# rc2014_3kb_ram.net
KiCad netlist of a schematic drawn in EAGLE
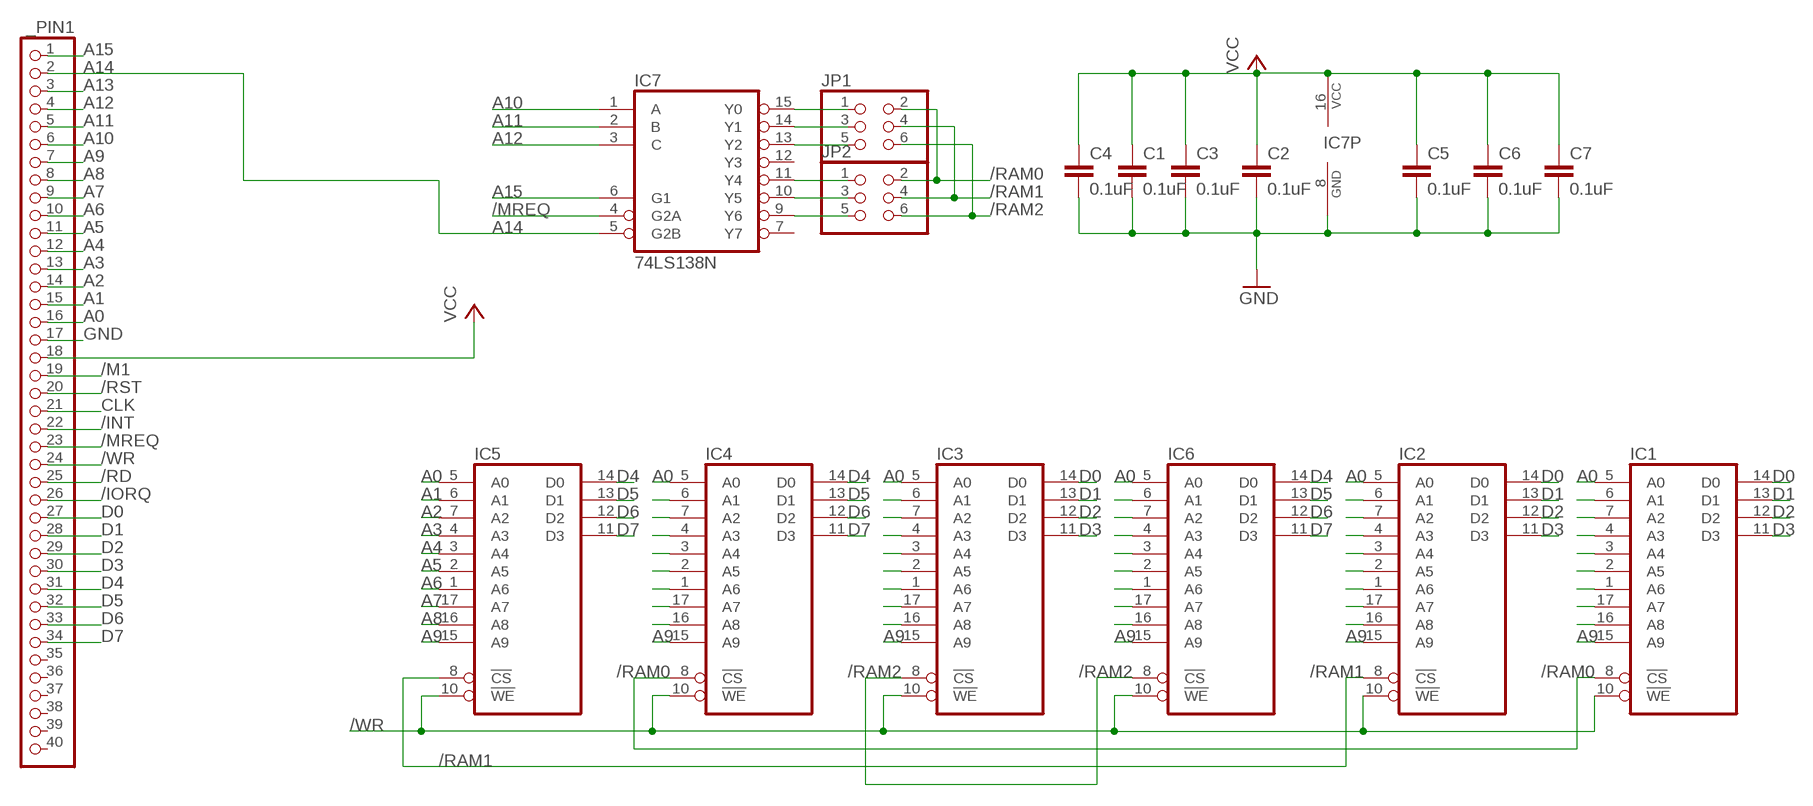
[diagram p0: schematic, sheet 1]

(export (version "E")
  (design (tool "Eeschema 10.0.6"))
  (components
    (comp (ref "C1")
      (value "0.1uF")
      (footprint "eagle-import:C050-024X044")
      (libsource (lib "eagle-import") (part "C-EU050-024X044"))
    )
    (comp (ref "C2")
      (value "0.1uF")
      (footprint "eagle-import:C050-024X044")
      (libsource (lib "eagle-import") (part "C-EU050-024X044"))
    )
    (comp (ref "C3")
      (value "0.1uF")
      (footprint "eagle-import:C050-024X044")
      (libsource (lib "eagle-import") (part "C-EU050-024X044"))
    )
    (comp (ref "C4")
      (value "0.1uF")
      (footprint "eagle-import:C050-024X044")
      (libsource (lib "eagle-import") (part "C-EU050-024X044"))
    )
    (comp (ref "C5")
      (value "0.1uF")
      (footprint "eagle-import:C050-024X044")
      (libsource (lib "eagle-import") (part "C-EU050-024X044"))
    )
    (comp (ref "C6")
      (value "0.1uF")
      (footprint "eagle-import:C050-024X044")
      (libsource (lib "eagle-import") (part "C-EU050-024X044"))
    )
    (comp (ref "C7")
      (value "0.1uF")
      (footprint "eagle-import:C050-024X044")
      (libsource (lib "eagle-import") (part "C-EU050-024X044"))
    )
    (comp (ref "IC1")
      (value "2114")
      (footprint "eagle-import:DIL18")
      (libsource (lib "eagle-import") (part "2114"))
    )
    (comp (ref "IC2")
      (value "2114")
      (footprint "eagle-import:DIL18")
      (libsource (lib "eagle-import") (part "2114"))
    )
    (comp (ref "IC3")
      (value "2114")
      (footprint "eagle-import:DIL18")
      (libsource (lib "eagle-import") (part "2114"))
    )
    (comp (ref "IC4")
      (value "2114")
      (footprint "eagle-import:DIL18")
      (libsource (lib "eagle-import") (part "2114"))
    )
    (comp (ref "IC5")
      (value "2114")
      (footprint "eagle-import:DIL18")
      (libsource (lib "eagle-import") (part "2114"))
    )
    (comp (ref "IC6")
      (value "2114")
      (footprint "eagle-import:DIL18")
      (libsource (lib "eagle-import") (part "2114"))
    )
    (comp (ref "IC7")
      (value "74LS138N")
      (footprint "eagle-import:DIL16")
      (libsource (lib "eagle-import") (part "74138NLS"))
    )
    (comp (ref "JP1")
      (value "PINHD-2X3")
      (footprint "eagle-import:2X03")
      (libsource (lib "eagle-import") (part "PINHD-2X3"))
    )
    (comp (ref "JP2")
      (value "PINHD-2X3")
      (footprint "eagle-import:2X03")
      (libsource (lib "eagle-import") (part "PINHD-2X3"))
    )
    (comp (ref "_PIN1")
      (value "PINHD-1X40")
      (footprint "eagle-import:1X40")
      (libsource (lib "eagle-import") (part "PINHD-1X40"))
    )
  )
  (nets
    (net (code "1") (name "/A0") (class "Default")
      (node (ref "IC1") (pin "5") (pinfunction "A0_5") (pintype "input"))
      (node (ref "IC2") (pin "5") (pinfunction "A0_5") (pintype "input"))
      (node (ref "IC3") (pin "5") (pinfunction "A0_5") (pintype "input"))
      (node (ref "IC4") (pin "5") (pinfunction "A0_5") (pintype "input"))
      (node (ref "IC5") (pin "5") (pinfunction "A0_5") (pintype "input"))
      (node (ref "IC6") (pin "5") (pinfunction "A0_5") (pintype "input"))
      (node (ref "_PIN1") (pin "16") (pinfunction "16_16") (pintype "passive"))
    )
    (net (code "2") (name "/A1") (class "Default")
      (node (ref "IC1") (pin "6") (pinfunction "A1_6") (pintype "input"))
      (node (ref "IC2") (pin "6") (pinfunction "A1_6") (pintype "input"))
      (node (ref "IC3") (pin "6") (pinfunction "A1_6") (pintype "input"))
      (node (ref "IC4") (pin "6") (pinfunction "A1_6") (pintype "input"))
      (node (ref "IC5") (pin "6") (pinfunction "A1_6") (pintype "input"))
      (node (ref "IC6") (pin "6") (pinfunction "A1_6") (pintype "input"))
      (node (ref "_PIN1") (pin "15") (pinfunction "15_15") (pintype "passive"))
    )
    (net (code "3") (name "/A2") (class "Default")
      (node (ref "IC1") (pin "7") (pinfunction "A2_7") (pintype "input"))
      (node (ref "IC2") (pin "7") (pinfunction "A2_7") (pintype "input"))
      (node (ref "IC3") (pin "7") (pinfunction "A2_7") (pintype "input"))
      (node (ref "IC4") (pin "7") (pinfunction "A2_7") (pintype "input"))
      (node (ref "IC5") (pin "7") (pinfunction "A2_7") (pintype "input"))
      (node (ref "IC6") (pin "7") (pinfunction "A2_7") (pintype "input"))
      (node (ref "_PIN1") (pin "14") (pinfunction "14_14") (pintype "passive"))
    )
    (net (code "4") (name "/A3") (class "Default")
      (node (ref "IC1") (pin "4") (pinfunction "A3_4") (pintype "input"))
      (node (ref "IC2") (pin "4") (pinfunction "A3_4") (pintype "input"))
      (node (ref "IC3") (pin "4") (pinfunction "A3_4") (pintype "input"))
      (node (ref "IC4") (pin "4") (pinfunction "A3_4") (pintype "input"))
      (node (ref "IC5") (pin "4") (pinfunction "A3_4") (pintype "input"))
      (node (ref "IC6") (pin "4") (pinfunction "A3_4") (pintype "input"))
      (node (ref "_PIN1") (pin "13") (pinfunction "13_13") (pintype "passive"))
    )
    (net (code "5") (name "/A4") (class "Default")
      (node (ref "IC1") (pin "3") (pinfunction "A4_3") (pintype "input"))
      (node (ref "IC2") (pin "3") (pinfunction "A4_3") (pintype "input"))
      (node (ref "IC3") (pin "3") (pinfunction "A4_3") (pintype "input"))
      (node (ref "IC4") (pin "3") (pinfunction "A4_3") (pintype "input"))
      (node (ref "IC5") (pin "3") (pinfunction "A4_3") (pintype "input"))
      (node (ref "IC6") (pin "3") (pinfunction "A4_3") (pintype "input"))
      (node (ref "_PIN1") (pin "12") (pinfunction "12_12") (pintype "passive"))
    )
    (net (code "6") (name "/A5") (class "Default")
      (node (ref "IC1") (pin "2") (pinfunction "A5_2") (pintype "input"))
      (node (ref "IC2") (pin "2") (pinfunction "A5_2") (pintype "input"))
      (node (ref "IC3") (pin "2") (pinfunction "A5_2") (pintype "input"))
      (node (ref "IC4") (pin "2") (pinfunction "A5_2") (pintype "input"))
      (node (ref "IC5") (pin "2") (pinfunction "A5_2") (pintype "input"))
      (node (ref "IC6") (pin "2") (pinfunction "A5_2") (pintype "input"))
      (node (ref "_PIN1") (pin "11") (pinfunction "11_11") (pintype "passive"))
    )
    (net (code "7") (name "/A6") (class "Default")
      (node (ref "IC1") (pin "1") (pinfunction "A6_1") (pintype "input"))
      (node (ref "IC2") (pin "1") (pinfunction "A6_1") (pintype "input"))
      (node (ref "IC3") (pin "1") (pinfunction "A6_1") (pintype "input"))
      (node (ref "IC4") (pin "1") (pinfunction "A6_1") (pintype "input"))
      (node (ref "IC5") (pin "1") (pinfunction "A6_1") (pintype "input"))
      (node (ref "IC6") (pin "1") (pinfunction "A6_1") (pintype "input"))
      (node (ref "_PIN1") (pin "10") (pinfunction "10_10") (pintype "passive"))
    )
    (net (code "8") (name "/A7") (class "Default")
      (node (ref "IC1") (pin "17") (pinfunction "A7_17") (pintype "input"))
      (node (ref "IC2") (pin "17") (pinfunction "A7_17") (pintype "input"))
      (node (ref "IC3") (pin "17") (pinfunction "A7_17") (pintype "input"))
      (node (ref "IC4") (pin "17") (pinfunction "A7_17") (pintype "input"))
      (node (ref "IC5") (pin "17") (pinfunction "A7_17") (pintype "input"))
      (node (ref "IC6") (pin "17") (pinfunction "A7_17") (pintype "input"))
      (node (ref "_PIN1") (pin "9") (pinfunction "9_9") (pintype "passive"))
    )
    (net (code "9") (name "/A8") (class "Default")
      (node (ref "IC1") (pin "16") (pinfunction "A8_16") (pintype "input"))
      (node (ref "IC2") (pin "16") (pinfunction "A8_16") (pintype "input"))
      (node (ref "IC3") (pin "16") (pinfunction "A8_16") (pintype "input"))
      (node (ref "IC4") (pin "16") (pinfunction "A8_16") (pintype "input"))
      (node (ref "IC5") (pin "16") (pinfunction "A8_16") (pintype "input"))
      (node (ref "IC6") (pin "16") (pinfunction "A8_16") (pintype "input"))
      (node (ref "_PIN1") (pin "8") (pinfunction "8_8") (pintype "passive"))
    )
    (net (code "10") (name "/A9") (class "Default")
      (node (ref "IC1") (pin "15") (pinfunction "A9_15") (pintype "input"))
      (node (ref "IC2") (pin "15") (pinfunction "A9_15") (pintype "input"))
      (node (ref "IC3") (pin "15") (pinfunction "A9_15") (pintype "input"))
      (node (ref "IC4") (pin "15") (pinfunction "A9_15") (pintype "input"))
      (node (ref "IC5") (pin "15") (pinfunction "A9_15") (pintype "input"))
      (node (ref "IC6") (pin "15") (pinfunction "A9_15") (pintype "input"))
      (node (ref "_PIN1") (pin "7") (pinfunction "7_7") (pintype "passive"))
    )
    (net (code "11") (name "/A10") (class "Default")
      (node (ref "IC7") (pin "1") (pinfunction "A_1") (pintype "input"))
      (node (ref "_PIN1") (pin "6") (pinfunction "6_6") (pintype "passive"))
    )
    (net (code "12") (name "/A11") (class "Default")
      (node (ref "IC7") (pin "2") (pinfunction "B_2") (pintype "input"))
      (node (ref "_PIN1") (pin "5") (pinfunction "5_5") (pintype "passive"))
    )
    (net (code "13") (name "/A12") (class "Default")
      (node (ref "IC7") (pin "3") (pinfunction "C_3") (pintype "input"))
      (node (ref "_PIN1") (pin "4") (pinfunction "4_4") (pintype "passive"))
    )
    (net (code "14") (name "/A13") (class "Default")
      (node (ref "_PIN1") (pin "3") (pinfunction "3_3") (pintype "passive"))
    )
    (net (code "15") (name "/A14") (class "Default")
      (node (ref "IC7") (pin "5") (pinfunction "G2B_5") (pintype "input"))
      (node (ref "_PIN1") (pin "2") (pinfunction "2_2") (pintype "passive"))
    )
    (net (code "16") (name "/A15") (class "Default")
      (node (ref "IC7") (pin "6") (pinfunction "G1_6") (pintype "input"))
      (node (ref "_PIN1") (pin "1") (pinfunction "1_1") (pintype "passive"))
    )
    (net (code "17") (name "/CLK") (class "Default")
      (node (ref "_PIN1") (pin "21") (pinfunction "21_21") (pintype "passive"))
    )
    (net (code "18") (name "/D0") (class "Default")
      (node (ref "IC1") (pin "14") (pinfunction "D0_14") (pintype "bidirectional"))
      (node (ref "IC2") (pin "14") (pinfunction "D0_14") (pintype "bidirectional"))
      (node (ref "IC3") (pin "14") (pinfunction "D0_14") (pintype "bidirectional"))
      (node (ref "_PIN1") (pin "27") (pinfunction "27_27") (pintype "passive"))
    )
    (net (code "19") (name "/D1") (class "Default")
      (node (ref "IC1") (pin "13") (pinfunction "D1_13") (pintype "bidirectional"))
      (node (ref "IC2") (pin "13") (pinfunction "D1_13") (pintype "bidirectional"))
      (node (ref "IC3") (pin "13") (pinfunction "D1_13") (pintype "bidirectional"))
      (node (ref "_PIN1") (pin "28") (pinfunction "28_28") (pintype "passive"))
    )
    (net (code "20") (name "/D2") (class "Default")
      (node (ref "IC1") (pin "12") (pinfunction "D2_12") (pintype "bidirectional"))
      (node (ref "IC2") (pin "12") (pinfunction "D2_12") (pintype "bidirectional"))
      (node (ref "IC3") (pin "12") (pinfunction "D2_12") (pintype "bidirectional"))
      (node (ref "_PIN1") (pin "29") (pinfunction "29_29") (pintype "passive"))
    )
    (net (code "21") (name "/D3") (class "Default")
      (node (ref "IC1") (pin "11") (pinfunction "D3_11") (pintype "bidirectional"))
      (node (ref "IC2") (pin "11") (pinfunction "D3_11") (pintype "bidirectional"))
      (node (ref "IC3") (pin "11") (pinfunction "D3_11") (pintype "bidirectional"))
      (node (ref "_PIN1") (pin "30") (pinfunction "30_30") (pintype "passive"))
    )
    (net (code "22") (name "/D4") (class "Default")
      (node (ref "IC4") (pin "14") (pinfunction "D0_14") (pintype "bidirectional"))
      (node (ref "IC5") (pin "14") (pinfunction "D0_14") (pintype "bidirectional"))
      (node (ref "IC6") (pin "14") (pinfunction "D0_14") (pintype "bidirectional"))
      (node (ref "_PIN1") (pin "31") (pinfunction "31_31") (pintype "passive"))
    )
    (net (code "23") (name "/D5") (class "Default")
      (node (ref "IC4") (pin "13") (pinfunction "D1_13") (pintype "bidirectional"))
      (node (ref "IC5") (pin "13") (pinfunction "D1_13") (pintype "bidirectional"))
      (node (ref "IC6") (pin "13") (pinfunction "D1_13") (pintype "bidirectional"))
      (node (ref "_PIN1") (pin "32") (pinfunction "32_32") (pintype "passive"))
    )
    (net (code "24") (name "/D6") (class "Default")
      (node (ref "IC4") (pin "12") (pinfunction "D2_12") (pintype "bidirectional"))
      (node (ref "IC5") (pin "12") (pinfunction "D2_12") (pintype "bidirectional"))
      (node (ref "IC6") (pin "12") (pinfunction "D2_12") (pintype "bidirectional"))
      (node (ref "_PIN1") (pin "33") (pinfunction "33_33") (pintype "passive"))
    )
    (net (code "25") (name "/D7") (class "Default")
      (node (ref "IC4") (pin "11") (pinfunction "D3_11") (pintype "bidirectional"))
      (node (ref "IC5") (pin "11") (pinfunction "D3_11") (pintype "bidirectional"))
      (node (ref "IC6") (pin "11") (pinfunction "D3_11") (pintype "bidirectional"))
      (node (ref "_PIN1") (pin "34") (pinfunction "34_34") (pintype "passive"))
    )
    (net (code "26") (name "/{slash}INT") (class "Default")
      (node (ref "_PIN1") (pin "22") (pinfunction "22_22") (pintype "passive"))
    )
    (net (code "27") (name "/{slash}IORQ") (class "Default")
      (node (ref "_PIN1") (pin "26") (pinfunction "26_26") (pintype "passive"))
    )
    (net (code "28") (name "/{slash}M1") (class "Default")
      (node (ref "_PIN1") (pin "19") (pinfunction "19_19") (pintype "passive"))
    )
    (net (code "29") (name "/{slash}MREQ") (class "Default")
      (node (ref "IC7") (pin "4") (pinfunction "G2A_4") (pintype "input"))
      (node (ref "_PIN1") (pin "23") (pinfunction "23_23") (pintype "passive"))
    )
    (net (code "30") (name "/{slash}RAM0") (class "Default")
      (node (ref "IC1") (pin "8") (pinfunction "~{CS}_8") (pintype "input"))
      (node (ref "IC4") (pin "8") (pinfunction "~{CS}_8") (pintype "input"))
      (node (ref "JP1") (pin "2") (pinfunction "2_2") (pintype "passive"))
      (node (ref "JP2") (pin "2") (pinfunction "2_2") (pintype "passive"))
    )
    (net (code "31") (name "/{slash}RAM1") (class "Default")
      (node (ref "IC2") (pin "8") (pinfunction "~{CS}_8") (pintype "input"))
      (node (ref "IC5") (pin "8") (pinfunction "~{CS}_8") (pintype "input"))
      (node (ref "JP1") (pin "4") (pinfunction "4_4") (pintype "passive"))
      (node (ref "JP2") (pin "4") (pinfunction "4_4") (pintype "passive"))
    )
    (net (code "32") (name "/{slash}RAM2") (class "Default")
      (node (ref "IC3") (pin "8") (pinfunction "~{CS}_8") (pintype "input"))
      (node (ref "IC6") (pin "8") (pinfunction "~{CS}_8") (pintype "input"))
      (node (ref "JP1") (pin "6") (pinfunction "6_6") (pintype "passive"))
      (node (ref "JP2") (pin "6") (pinfunction "6_6") (pintype "passive"))
    )
    (net (code "33") (name "/{slash}RD") (class "Default")
      (node (ref "_PIN1") (pin "25") (pinfunction "25_25") (pintype "passive"))
    )
    (net (code "34") (name "/{slash}RST") (class "Default")
      (node (ref "_PIN1") (pin "20") (pinfunction "20_20") (pintype "passive"))
    )
    (net (code "35") (name "/{slash}WR") (class "Default")
      (node (ref "IC1") (pin "10") (pinfunction "~{WE}_10") (pintype "input"))
      (node (ref "IC2") (pin "10") (pinfunction "~{WE}_10") (pintype "input"))
      (node (ref "IC3") (pin "10") (pinfunction "~{WE}_10") (pintype "input"))
      (node (ref "IC4") (pin "10") (pinfunction "~{WE}_10") (pintype "input"))
      (node (ref "IC5") (pin "10") (pinfunction "~{WE}_10") (pintype "input"))
      (node (ref "IC6") (pin "10") (pinfunction "~{WE}_10") (pintype "input"))
      (node (ref "_PIN1") (pin "24") (pinfunction "24_24") (pintype "passive"))
    )
    (net (code "36") (name "GND") (class "Default")
      (node (ref "C1") (pin "2") (pinfunction "2_2") (pintype "passive"))
      (node (ref "C2") (pin "2") (pinfunction "2_2") (pintype "passive"))
      (node (ref "C3") (pin "2") (pinfunction "2_2") (pintype "passive"))
      (node (ref "C4") (pin "2") (pinfunction "2_2") (pintype "passive"))
      (node (ref "C5") (pin "2") (pinfunction "2_2") (pintype "passive"))
      (node (ref "C6") (pin "2") (pinfunction "2_2") (pintype "passive"))
      (node (ref "C7") (pin "2") (pinfunction "2_2") (pintype "passive"))
      (node (ref "IC7") (pin "8") (pinfunction "GND_8") (pintype "power_in"))
      (node (ref "_PIN1") (pin "17") (pinfunction "17_17") (pintype "passive"))
    )
    (net (code "37") (name "Net-(IC7A-Y0)") (class "Default")
      (node (ref "IC7") (pin "15") (pinfunction "Y0_15") (pintype "output"))
      (node (ref "JP1") (pin "1") (pinfunction "1_1") (pintype "passive"))
    )
    (net (code "38") (name "Net-(IC7A-Y1)") (class "Default")
      (node (ref "IC7") (pin "14") (pinfunction "Y1_14") (pintype "output"))
      (node (ref "JP1") (pin "3") (pinfunction "3_3") (pintype "passive"))
    )
    (net (code "39") (name "Net-(IC7A-Y2)") (class "Default")
      (node (ref "IC7") (pin "13") (pinfunction "Y2_13") (pintype "output"))
      (node (ref "JP1") (pin "5") (pinfunction "5_5") (pintype "passive"))
    )
    (net (code "40") (name "Net-(IC7A-Y4)") (class "Default")
      (node (ref "IC7") (pin "11") (pinfunction "Y4_11") (pintype "output"))
      (node (ref "JP2") (pin "1") (pinfunction "1_1") (pintype "passive"))
    )
    (net (code "41") (name "Net-(IC7A-Y5)") (class "Default")
      (node (ref "IC7") (pin "10") (pinfunction "Y5_10") (pintype "output"))
      (node (ref "JP2") (pin "3") (pinfunction "3_3") (pintype "passive"))
    )
    (net (code "42") (name "Net-(IC7A-Y6)") (class "Default")
      (node (ref "IC7") (pin "9") (pinfunction "Y6_9") (pintype "output"))
      (node (ref "JP2") (pin "5") (pinfunction "5_5") (pintype "passive"))
    )
    (net (code "43") (name "VCC") (class "Default")
      (node (ref "C1") (pin "1") (pinfunction "1_1") (pintype "passive"))
      (node (ref "C2") (pin "1") (pinfunction "1_1") (pintype "passive"))
      (node (ref "C3") (pin "1") (pinfunction "1_1") (pintype "passive"))
      (node (ref "C4") (pin "1") (pinfunction "1_1") (pintype "passive"))
      (node (ref "C5") (pin "1") (pinfunction "1_1") (pintype "passive"))
      (node (ref "C6") (pin "1") (pinfunction "1_1") (pintype "passive"))
      (node (ref "C7") (pin "1") (pinfunction "1_1") (pintype "passive"))
      (node (ref "IC7") (pin "16") (pinfunction "VCC_16") (pintype "power_in"))
      (node (ref "_PIN1") (pin "18") (pinfunction "18_18") (pintype "passive"))
    )
    (net (code "44") (name "unconnected-(IC7A-Y3-Pad12)") (class "Default")
      (node (ref "IC7") (pin "12") (pinfunction "Y3_12") (pintype "output"))
    )
    (net (code "45") (name "unconnected-(IC7A-Y7-Pad7)") (class "Default")
      (node (ref "IC7") (pin "7") (pinfunction "Y7_7") (pintype "output"))
    )
    (net (code "46") (name "unconnected-(_PIN1-Pad35)") (class "Default")
      (node (ref "_PIN1") (pin "35") (pinfunction "35_35") (pintype "passive"))
    )
    (net (code "47") (name "unconnected-(_PIN1-Pad36)") (class "Default")
      (node (ref "_PIN1") (pin "36") (pinfunction "36_36") (pintype "passive"))
    )
    (net (code "48") (name "unconnected-(_PIN1-Pad37)") (class "Default")
      (node (ref "_PIN1") (pin "37") (pinfunction "37_37") (pintype "passive"))
    )
    (net (code "49") (name "unconnected-(_PIN1-Pad38)") (class "Default")
      (node (ref "_PIN1") (pin "38") (pinfunction "38_38") (pintype "passive"))
    )
    (net (code "50") (name "unconnected-(_PIN1-Pad39)") (class "Default")
      (node (ref "_PIN1") (pin "39") (pinfunction "39_39") (pintype "passive"))
    )
    (net (code "51") (name "unconnected-(_PIN1-Pad40)") (class "Default")
      (node (ref "_PIN1") (pin "40") (pinfunction "40_40") (pintype "passive"))
    )
  )
)
